# circuitdraft.net
KiCad netlist of a schematic drawn in EAGLE
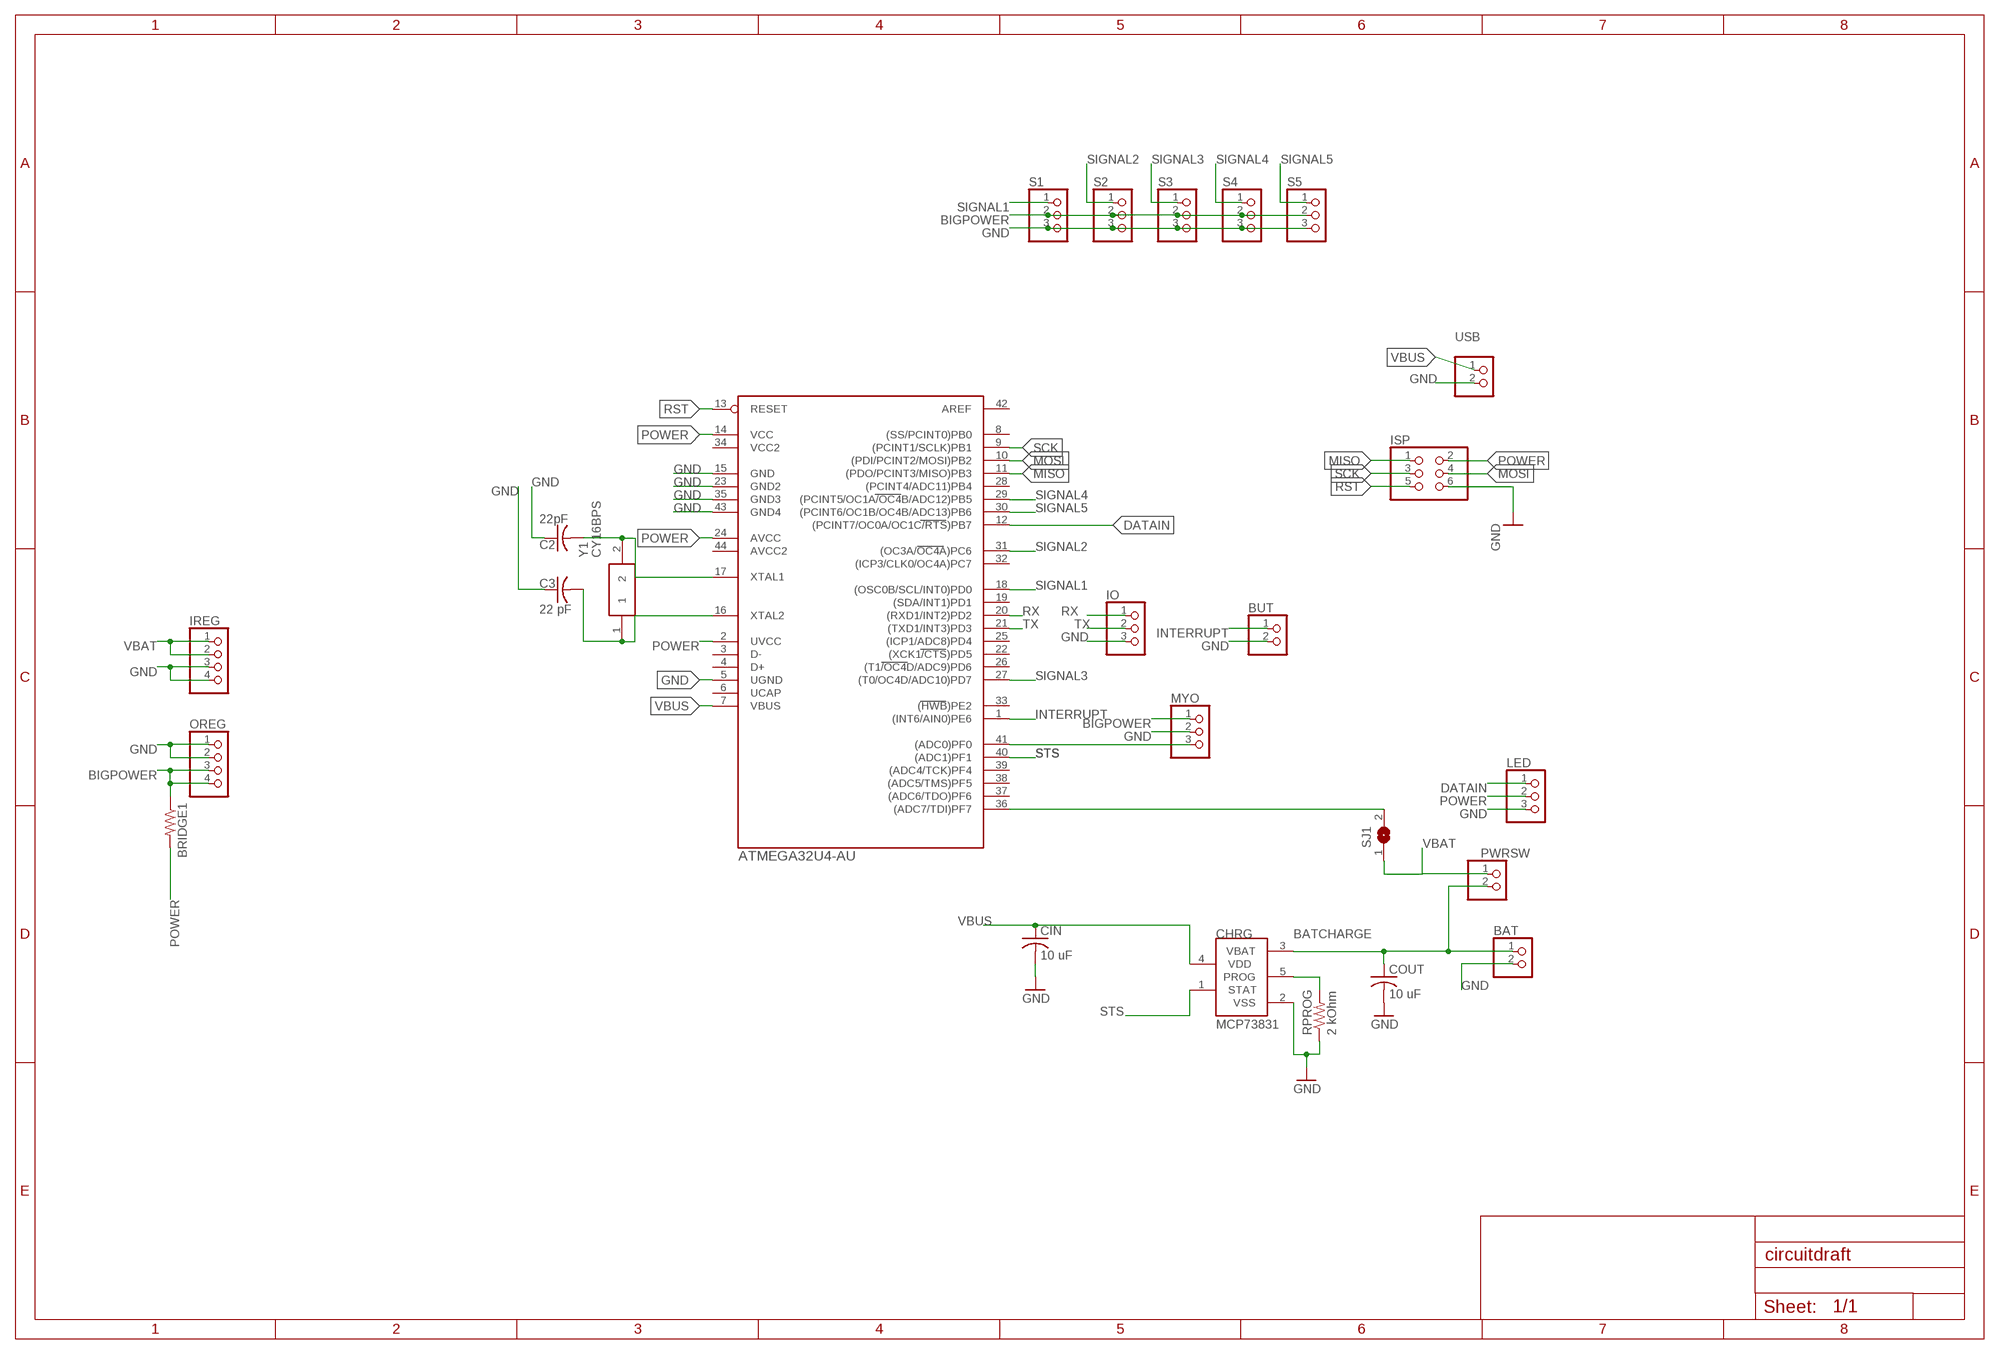
[diagram p0: schematic, sheet 1]

(export (version "E")
  (design (tool "Eeschema 10.0.6"))
  (components
    (comp (ref "BAT")
      (value "PINHD-1X2")
      (footprint "eagle-import:1X02")
      (libsource (lib "eagle-import") (part "PINHD-1X2"))
    )
    (comp (ref "BRIDGE1")
      (value "R-US_M0805")
      (footprint "eagle-import:M0805")
      (libsource (lib "eagle-import") (part "R-US_M0805"))
    )
    (comp (ref "BUT")
      (value "PINHD-1X2")
      (footprint "eagle-import:1X02")
      (libsource (lib "eagle-import") (part "PINHD-1X2"))
    )
    (comp (ref "C2")
      (value "22pF")
      (footprint "eagle-import:C025-024X044")
      (libsource (lib "eagle-import") (part "C-US025-024X044"))
    )
    (comp (ref "C3")
      (value "22 pF")
      (footprint "eagle-import:C025-024X044")
      (libsource (lib "eagle-import") (part "C-US025-024X044"))
    )
    (comp (ref "CHRG")
      (value "MCP73831")
      (footprint "eagle-import:SOT23-5L")
      (libsource (lib "eagle-import") (part "MCP73831"))
    )
    (comp (ref "CIN")
      (value "10 uF")
      (footprint "eagle-import:C0603")
      (libsource (lib "eagle-import") (part "C-USC0603"))
    )
    (comp (ref "COUT")
      (value "10 uF")
      (footprint "eagle-import:C0603")
      (libsource (lib "eagle-import") (part "C-USC0603"))
    )
    (comp (ref "IO")
      (value "PINHD-1X3")
      (footprint "eagle-import:1X03")
      (libsource (lib "eagle-import") (part "PINHD-1X3"))
    )
    (comp (ref "IREG")
      (value "PINHD-1X4")
      (footprint "eagle-import:1X04")
      (libsource (lib "eagle-import") (part "PINHD-1X4"))
    )
    (comp (ref "ISP")
      (value "PINHD-2X3")
      (footprint "eagle-import:2X03")
      (libsource (lib "eagle-import") (part "PINHD-2X3"))
    )
    (comp (ref "LED")
      (value "PINHD-1X3")
      (footprint "eagle-import:1X03")
      (libsource (lib "eagle-import") (part "PINHD-1X3"))
    )
    (comp (ref "MYO")
      (value "PINHD-1X3")
      (footprint "eagle-import:1X03")
      (libsource (lib "eagle-import") (part "PINHD-1X3"))
    )
    (comp (ref "OREG")
      (value "PINHD-1X4")
      (footprint "eagle-import:1X04")
      (libsource (lib "eagle-import") (part "PINHD-1X4"))
    )
    (comp (ref "PWRSW")
      (value "PINHD-1X2")
      (footprint "eagle-import:1X02")
      (libsource (lib "eagle-import") (part "PINHD-1X2"))
    )
    (comp (ref "RPROG")
      (value "2 kOhm")
      (footprint "eagle-import:R0603")
      (libsource (lib "eagle-import") (part "R-US_R0603"))
    )
    (comp (ref "S1")
      (value "PINHD-1X3")
      (footprint "eagle-import:1X03")
      (libsource (lib "eagle-import") (part "PINHD-1X3"))
    )
    (comp (ref "S2")
      (value "PINHD-1X3")
      (footprint "eagle-import:1X03")
      (libsource (lib "eagle-import") (part "PINHD-1X3"))
    )
    (comp (ref "S3")
      (value "PINHD-1X3")
      (footprint "eagle-import:1X03")
      (libsource (lib "eagle-import") (part "PINHD-1X3"))
    )
    (comp (ref "S4")
      (value "PINHD-1X3")
      (footprint "eagle-import:1X03")
      (libsource (lib "eagle-import") (part "PINHD-1X3"))
    )
    (comp (ref "S5")
      (value "PINHD-1X3")
      (footprint "eagle-import:1X03")
      (libsource (lib "eagle-import") (part "PINHD-1X3"))
    )
    (comp (ref "SJ1") (value "SJ") (footprint "eagle-import:SJ") (libsource (lib "eagle-import") (part "SJ")))
    (comp (ref "U$1")
      (value "ATMEGA32U4-AU")
      (footprint "eagle-import:TQFP44")
      (libsource (lib "eagle-import") (part "ATMEGA32U4-AU"))
    )
    (comp (ref "USB")
      (value "PINHD-1X2")
      (footprint "eagle-import:1X02")
      (libsource (lib "eagle-import") (part "PINHD-1X2"))
    )
    (comp (ref "Y1")
      (value "CY16BPS")
      (footprint "eagle-import:CY16BPS")
      (fields (field (name "MOUSER_PART_NUMBER") "549-CY16BPS"))
      (libsource (lib "eagle-import") (part "CY16BPS"))
    )
  )
  (nets
    (net (code "1") (name "/BATCHARGE") (class "Default")
      (node (ref "BAT") (pin "1") (pinfunction "1_1") (pintype "passive"))
      (node (ref "CHRG") (pin "3") (pinfunction "VBAT_3") (pintype "bidirectional"))
      (node (ref "COUT") (pin "1") (pinfunction "1_1") (pintype "passive"))
      (node (ref "PWRSW") (pin "2") (pinfunction "2_2") (pintype "passive"))
    )
    (net (code "2") (name "/BIGPOWER") (class "Default")
      (node (ref "BRIDGE1") (pin "1") (pinfunction "1_1") (pintype "passive"))
      (node (ref "MYO") (pin "1") (pinfunction "1_1") (pintype "passive"))
      (node (ref "OREG") (pin "3") (pinfunction "3_3") (pintype "passive"))
      (node (ref "OREG") (pin "4") (pinfunction "4_4") (pintype "passive"))
      (node (ref "S1") (pin "2") (pinfunction "2_2") (pintype "passive"))
      (node (ref "S2") (pin "2") (pinfunction "2_2") (pintype "passive"))
      (node (ref "S3") (pin "2") (pinfunction "2_2") (pintype "passive"))
      (node (ref "S4") (pin "2") (pinfunction "2_2") (pintype "passive"))
      (node (ref "S5") (pin "2") (pinfunction "2_2") (pintype "passive"))
    )
    (net (code "3") (name "/INTERRUPT") (class "Default")
      (node (ref "BUT") (pin "1") (pinfunction "1_1") (pintype "passive"))
      (node (ref "U$1") (pin "1") (pinfunction "(INT6/AIN0)PE6_1") (pintype "bidirectional"))
    )
    (net (code "4") (name "/RX") (class "Default")
      (node (ref "IO") (pin "1") (pinfunction "1_1") (pintype "passive"))
      (node (ref "U$1") (pin "20") (pinfunction "(RXD1/INT2)PD2_20") (pintype "bidirectional"))
    )
    (net (code "5") (name "/SIGNAL1") (class "Default")
      (node (ref "S1") (pin "1") (pinfunction "1_1") (pintype "passive"))
      (node (ref "U$1") (pin "18") (pinfunction "(OSC0B/SCL/INT0)PD0_18") (pintype "bidirectional"))
    )
    (net (code "6") (name "/SIGNAL2") (class "Default")
      (node (ref "S2") (pin "1") (pinfunction "1_1") (pintype "passive"))
      (node (ref "U$1") (pin "31") (pinfunction "(OC3A/OC4A)PC6_31") (pintype "bidirectional"))
    )
    (net (code "7") (name "/SIGNAL3") (class "Default")
      (node (ref "S3") (pin "1") (pinfunction "1_1") (pintype "passive"))
      (node (ref "U$1") (pin "27") (pinfunction "(T0/OC4D/ADC10)PD7_27") (pintype "bidirectional"))
    )
    (net (code "8") (name "/SIGNAL4") (class "Default")
      (node (ref "S4") (pin "1") (pinfunction "1_1") (pintype "passive"))
      (node (ref "U$1") (pin "29") (pinfunction "(PCINT5/OC1A/OC4B/ADC12)PB5_29") (pintype "bidirectional"))
    )
    (net (code "9") (name "/SIGNAL5") (class "Default")
      (node (ref "S5") (pin "1") (pinfunction "1_1") (pintype "passive"))
      (node (ref "U$1") (pin "30") (pinfunction "(PCINT6/OC1B/OC4B/ADC13)PB6_30") (pintype "bidirectional"))
    )
    (net (code "10") (name "/STS") (class "Default")
      (node (ref "CHRG") (pin "1") (pinfunction "STAT_1") (pintype "bidirectional"))
      (node (ref "U$1") (pin "40") (pinfunction "(ADC1)PF1_40") (pintype "bidirectional"))
    )
    (net (code "11") (name "/TX") (class "Default")
      (node (ref "IO") (pin "2") (pinfunction "2_2") (pintype "passive"))
      (node (ref "U$1") (pin "21") (pinfunction "(TXD1/INT3)PD3_21") (pintype "bidirectional"))
    )
    (net (code "12") (name "/VBAT") (class "Default")
      (node (ref "IREG") (pin "1") (pinfunction "1_1") (pintype "passive"))
      (node (ref "IREG") (pin "2") (pinfunction "2_2") (pintype "passive"))
      (node (ref "PWRSW") (pin "1") (pinfunction "1_1") (pintype "passive"))
      (node (ref "SJ1") (pin "1") (pinfunction "1_1") (pintype "passive"))
    )
    (net (code "13") (name "DATAIN") (class "Default")
      (node (ref "LED") (pin "1") (pinfunction "1_1") (pintype "passive"))
      (node (ref "U$1") (pin "12") (pinfunction "(PCINT7/OC0A/OC1C/RTS)PB7_12") (pintype "bidirectional"))
    )
    (net (code "14") (name "GND") (class "Default")
      (node (ref "BAT") (pin "2") (pinfunction "2_2") (pintype "passive"))
      (node (ref "BUT") (pin "2") (pinfunction "2_2") (pintype "passive"))
      (node (ref "C2") (pin "1") (pinfunction "1_1") (pintype "passive"))
      (node (ref "C3") (pin "1") (pinfunction "1_1") (pintype "passive"))
      (node (ref "CHRG") (pin "2") (pinfunction "VSS_2") (pintype "bidirectional"))
      (node (ref "CIN") (pin "2") (pinfunction "2_2") (pintype "passive"))
      (node (ref "COUT") (pin "2") (pinfunction "2_2") (pintype "passive"))
      (node (ref "IO") (pin "3") (pinfunction "3_3") (pintype "passive"))
      (node (ref "IREG") (pin "3") (pinfunction "3_3") (pintype "passive"))
      (node (ref "IREG") (pin "4") (pinfunction "4_4") (pintype "passive"))
      (node (ref "ISP") (pin "6") (pinfunction "6_6") (pintype "passive"))
      (node (ref "LED") (pin "3") (pinfunction "3_3") (pintype "passive"))
      (node (ref "MYO") (pin "2") (pinfunction "2_2") (pintype "passive"))
      (node (ref "OREG") (pin "1") (pinfunction "1_1") (pintype "passive"))
      (node (ref "OREG") (pin "2") (pinfunction "2_2") (pintype "passive"))
      (node (ref "RPROG") (pin "1") (pinfunction "1_1") (pintype "passive"))
      (node (ref "S1") (pin "3") (pinfunction "3_3") (pintype "passive"))
      (node (ref "S2") (pin "3") (pinfunction "3_3") (pintype "passive"))
      (node (ref "S3") (pin "3") (pinfunction "3_3") (pintype "passive"))
      (node (ref "S4") (pin "3") (pinfunction "3_3") (pintype "passive"))
      (node (ref "S5") (pin "3") (pinfunction "3_3") (pintype "passive"))
      (node (ref "U$1") (pin "15") (pinfunction "GND_15") (pintype "bidirectional"))
      (node (ref "U$1") (pin "23") (pinfunction "GND2_23") (pintype "bidirectional"))
      (node (ref "U$1") (pin "35") (pinfunction "GND3_35") (pintype "bidirectional"))
      (node (ref "U$1") (pin "43") (pinfunction "GND4_43") (pintype "bidirectional"))
      (node (ref "U$1") (pin "5") (pinfunction "UGND_5") (pintype "bidirectional"))
      (node (ref "USB") (pin "2") (pinfunction "2_2") (pintype "passive"))
    )
    (net (code "15") (name "MISO") (class "Default")
      (node (ref "ISP") (pin "1") (pinfunction "1_1") (pintype "passive"))
      (node (ref "U$1") (pin "11") (pinfunction "(PDO/PCINT3/MISO)PB3_11") (pintype "bidirectional"))
    )
    (net (code "16") (name "MOSI") (class "Default")
      (node (ref "ISP") (pin "4") (pinfunction "4_4") (pintype "passive"))
      (node (ref "U$1") (pin "10") (pinfunction "(PDI/PCINT2/MOSI)PB2_10") (pintype "bidirectional"))
    )
    (net (code "17") (name "Net-(CHRG-PROG)") (class "Default")
      (node (ref "CHRG") (pin "5") (pinfunction "PROG_5") (pintype "bidirectional"))
      (node (ref "RPROG") (pin "2") (pinfunction "2_2") (pintype "passive"))
    )
    (net (code "18") (name "Net-(U$1-(ADC0)PF0)") (class "Default")
      (node (ref "MYO") (pin "3") (pinfunction "3_3") (pintype "passive"))
      (node (ref "U$1") (pin "41") (pinfunction "(ADC0)PF0_41") (pintype "bidirectional"))
    )
    (net (code "19") (name "Net-(U$1-(ADC7{slash}TDI)PF7)") (class "Default")
      (node (ref "SJ1") (pin "2") (pinfunction "2_2") (pintype "passive"))
      (node (ref "U$1") (pin "36") (pinfunction "(ADC7/TDI)PF7_36") (pintype "bidirectional"))
    )
    (net (code "20") (name "Net-(U$1-XTAL1)") (class "Default")
      (node (ref "C2") (pin "2") (pinfunction "2_2") (pintype "passive"))
      (node (ref "U$1") (pin "17") (pinfunction "XTAL1_17") (pintype "bidirectional"))
      (node (ref "Y1") (pin "2") (pinfunction "2_2") (pintype "bidirectional"))
    )
    (net (code "21") (name "Net-(U$1-XTAL2)") (class "Default")
      (node (ref "C3") (pin "2") (pinfunction "2_2") (pintype "passive"))
      (node (ref "U$1") (pin "16") (pinfunction "XTAL2_16") (pintype "bidirectional"))
      (node (ref "Y1") (pin "1") (pinfunction "1_1") (pintype "bidirectional"))
    )
    (net (code "22") (name "POWER") (class "Default")
      (node (ref "BRIDGE1") (pin "2") (pinfunction "2_2") (pintype "passive"))
      (node (ref "ISP") (pin "2") (pinfunction "2_2") (pintype "passive"))
      (node (ref "LED") (pin "2") (pinfunction "2_2") (pintype "passive"))
      (node (ref "U$1") (pin "14") (pinfunction "VCC_14") (pintype "bidirectional"))
      (node (ref "U$1") (pin "2") (pinfunction "UVCC_2") (pintype "bidirectional"))
      (node (ref "U$1") (pin "24") (pinfunction "AVCC_24") (pintype "bidirectional"))
    )
    (net (code "23") (name "RST") (class "Default")
      (node (ref "ISP") (pin "5") (pinfunction "5_5") (pintype "passive"))
      (node (ref "U$1") (pin "13") (pinfunction "RESET_13") (pintype "bidirectional"))
    )
    (net (code "24") (name "SCK") (class "Default")
      (node (ref "ISP") (pin "3") (pinfunction "3_3") (pintype "passive"))
      (node (ref "U$1") (pin "9") (pinfunction "(PCINT1/SCLK)PB1_9") (pintype "bidirectional"))
    )
    (net (code "25") (name "VBUS") (class "Default")
      (node (ref "CHRG") (pin "4") (pinfunction "VDD_4") (pintype "bidirectional"))
      (node (ref "CIN") (pin "1") (pinfunction "1_1") (pintype "passive"))
      (node (ref "U$1") (pin "7") (pinfunction "VBUS_7") (pintype "bidirectional"))
      (node (ref "USB") (pin "1") (pinfunction "1_1") (pintype "passive"))
    )
    (net (code "26") (name "unconnected-(U$1-(ADC4{slash}TCK)PF4-Pad39)") (class "Default")
      (node (ref "U$1") (pin "39") (pinfunction "(ADC4/TCK)PF4_39") (pintype "bidirectional"))
    )
    (net (code "27") (name "unconnected-(U$1-(ADC5{slash}TMS)PF5-Pad38)") (class "Default")
      (node (ref "U$1") (pin "38") (pinfunction "(ADC5/TMS)PF5_38") (pintype "bidirectional"))
    )
    (net (code "28") (name "unconnected-(U$1-(ADC6{slash}TDO)PF6-Pad37)") (class "Default")
      (node (ref "U$1") (pin "37") (pinfunction "(ADC6/TDO)PF6_37") (pintype "bidirectional"))
    )
    (net (code "29") (name "unconnected-(U$1-(HWB)PE2-Pad33)") (class "Default")
      (node (ref "U$1") (pin "33") (pinfunction "(HWB)PE2_33") (pintype "bidirectional"))
    )
    (net (code "30") (name "unconnected-(U$1-(ICP1{slash}ADC8)PD4-Pad25)") (class "Default")
      (node (ref "U$1") (pin "25") (pinfunction "(ICP1/ADC8)PD4_25") (pintype "bidirectional"))
    )
    (net (code "31") (name "unconnected-(U$1-(ICP3{slash}CLK0{slash}OC4A)PC7-Pad32)") (class "Default")
      (node (ref "U$1") (pin "32") (pinfunction "(ICP3/CLK0/OC4A)PC7_32") (pintype "bidirectional"))
    )
    (net (code "32") (name "unconnected-(U$1-(PCINT4{slash}ADC11)PB4-Pad28)") (class "Default")
      (node (ref "U$1") (pin "28") (pinfunction "(PCINT4/ADC11)PB4_28") (pintype "bidirectional"))
    )
    (net (code "33") (name "unconnected-(U$1-(SDA{slash}INT1)PD1-Pad19)") (class "Default")
      (node (ref "U$1") (pin "19") (pinfunction "(SDA/INT1)PD1_19") (pintype "bidirectional"))
    )
    (net (code "34") (name "unconnected-(U$1-(SS{slash}PCINT0)PB0-Pad8)") (class "Default")
      (node (ref "U$1") (pin "8") (pinfunction "(SS/PCINT0)PB0_8") (pintype "bidirectional"))
    )
    (net (code "35") (name "unconnected-(U$1-(T1{slash}OC4D{slash}ADC9)PD6-Pad26)") (class "Default")
      (node (ref "U$1") (pin "26") (pinfunction "(T1/OC4D/ADC9)PD6_26") (pintype "bidirectional"))
    )
    (net (code "36") (name "unconnected-(U$1-(XCK1{slash}CTS)PD5-Pad22)") (class "Default")
      (node (ref "U$1") (pin "22") (pinfunction "(XCK1/CTS)PD5_22") (pintype "bidirectional"))
    )
    (net (code "37") (name "unconnected-(U$1-AREF-Pad42)") (class "Default")
      (node (ref "U$1") (pin "42") (pinfunction "AREF_42") (pintype "bidirectional"))
    )
    (net (code "38") (name "unconnected-(U$1-AVCC2-Pad44)") (class "Default")
      (node (ref "U$1") (pin "44") (pinfunction "AVCC2_44") (pintype "bidirectional"))
    )
    (net (code "39") (name "unconnected-(U$1-D+-Pad4)") (class "Default")
      (node (ref "U$1") (pin "4") (pinfunction "D+_4") (pintype "bidirectional"))
    )
    (net (code "40") (name "unconnected-(U$1-D--Pad3)") (class "Default")
      (node (ref "U$1") (pin "3") (pinfunction "D-_3") (pintype "bidirectional"))
    )
    (net (code "41") (name "unconnected-(U$1-UCAP-Pad6)") (class "Default")
      (node (ref "U$1") (pin "6") (pinfunction "UCAP_6") (pintype "bidirectional"))
    )
    (net (code "42") (name "unconnected-(U$1-VCC2-Pad34)") (class "Default")
      (node (ref "U$1") (pin "34") (pinfunction "VCC2_34") (pintype "bidirectional"))
    )
  )
)
